# TopLevel.net
KiCad netlist of a schematic drawn in Altium Designer
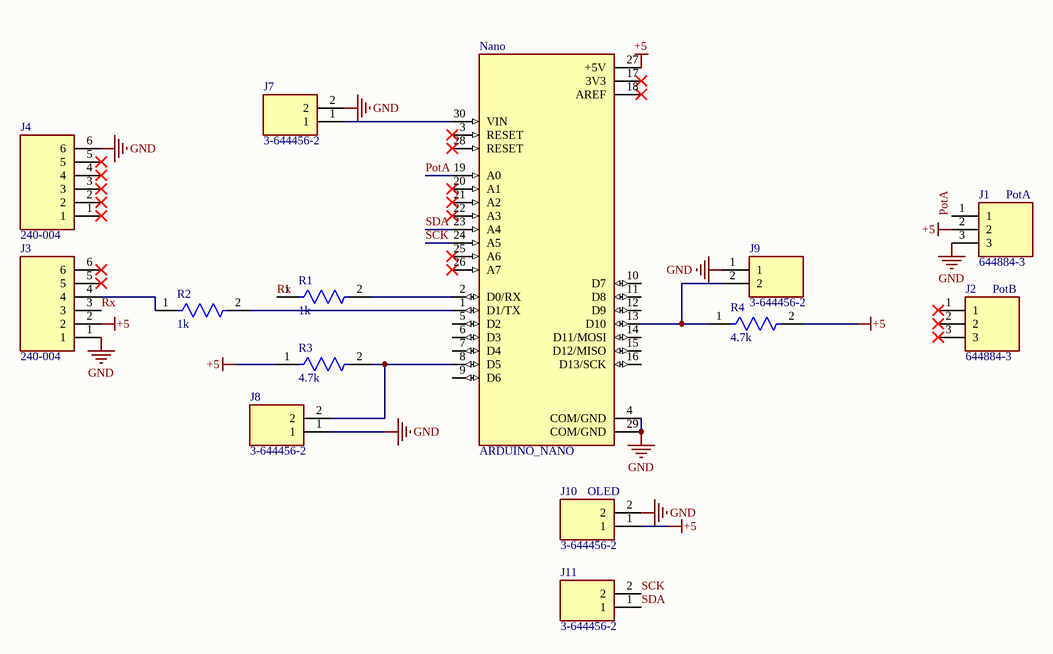
[diagram p0: TopLevel.SchDoc]

(export (version "E")
  (design (tool "Eeschema 10.0.6"))
  (components
    (comp (ref "J1")
      (value "644884-3")
      (footprint "TE_644884-3")
      (libsource (lib "Ryusei Kinosaki") (part "644884-3"))
    )
    (comp (ref "J2")
      (value "644884-3")
      (footprint "TE_644884-3")
      (libsource (lib "Ryusei Kinosaki") (part "644884-3"))
    )
    (comp (ref "J3")
      (value "240-004")
      (footprint "SamacSys:HDRV6W64P0X254_1X6_1524X254X909P")
      (description "Connector")
      (libsource (lib "*") (part "240-004"))
    )
    (comp (ref "J4")
      (value "240-004")
      (footprint "SamacSys:HDRV6W64P0X254_1X6_1524X254X909P")
      (description "Connector")
      (libsource (lib "*") (part "240-004"))
    )
    (comp (ref "J7")
      (value "3-644456-2")
      (footprint "TE_3-644456-2")
      (description "Connector Unshrouded Header HDR 2 Position 2.54mm Solder Straight Thru-Hole")
      (fields (field (name "MF") "TE Connectivity") (field (name "DIGI-KEY_PART_NUMBER") "A31112-ND"))
      (libsource (lib "Ryusei Kinosaki") (part "3-644456-2"))
    )
    (comp (ref "J8")
      (value "3-644456-2")
      (footprint "TE_3-644456-2")
      (description "Connector Unshrouded Header HDR 2 Position 2.54mm Solder Straight Thru-Hole")
      (fields (field (name "MF") "TE Connectivity") (field (name "DIGI-KEY_PART_NUMBER") "A31112-ND"))
      (libsource (lib "Ryusei Kinosaki") (part "3-644456-2"))
    )
    (comp (ref "J9")
      (value "3-644456-2")
      (footprint "TE_3-644456-2")
      (description "Connector Unshrouded Header HDR 2 Position 2.54mm Solder Straight Thru-Hole")
      (fields (field (name "MF") "TE Connectivity") (field (name "DIGI-KEY_PART_NUMBER") "A31112-ND"))
      (libsource (lib "") (part "3-644456-2_1"))
    )
    (comp (ref "J10")
      (value "3-644456-2")
      (footprint "TE_3-644456-2")
      (description "Connector Unshrouded Header HDR 2 Position 2.54mm Solder Straight Thru-Hole")
      (fields (field (name "MF") "TE Connectivity") (field (name "DIGI-KEY_PART_NUMBER") "A31112-ND"))
      (libsource (lib "Ryusei Kinosaki") (part "3-644456-2"))
    )
    (comp (ref "J11")
      (value "3-644456-2")
      (footprint "TE_3-644456-2")
      (description "Connector Unshrouded Header HDR 2 Position 2.54mm Solder Straight Thru-Hole")
      (fields (field (name "MF") "TE Connectivity") (field (name "DIGI-KEY_PART_NUMBER") "A31112-ND"))
      (libsource (lib "Ryusei Kinosaki") (part "3-644456-2"))
    )
    (comp (ref "Nano")
      (value "ARDUINO_NANO")
      (footprint "SHIELD_ARDUINO_NANO")
      (description "Small, complete, and breadboard-friendly board based on the ATmega328 (Arduino Nano 3.x)")
      (fields (field (name "MF") "Arduino") (field (name "MP") "Arduino Nano"))
      (libsource (lib "Ryusei Kinosaki") (part "ARDUINO_NANO"))
    )
    (comp (ref "R1")
      (value "MRS25000C1001FCT00")
      (footprint "FP-MRS25-MFG")
      (description "RES 1K OHM 0.6W 1% AXIAL")
      (fields (field (name "TOLERANCE") "1%") (field (name "RESISTANCE") "1k"))
      (libsource (lib "Altium Content Vault") (part "1029c3af85768c4190bb7ad29bc67b5"))
    )
    (comp (ref "R2")
      (value "MRS25000C1001FCT00")
      (footprint "FP-MRS25-MFG")
      (description "RES 1K OHM 0.6W 1% AXIAL")
      (fields (field (name "TOLERANCE") "1%") (field (name "RESISTANCE") "1k"))
      (libsource (lib "Altium Content Vault") (part "1029c3af85768c4190bb7ad29bc67b5"))
    )
    (comp (ref "R3")
      (value "MRS25000C1001FCT00")
      (footprint "FP-MRS25-MFG")
      (description "RES 1K OHM 0.6W 1% AXIAL")
      (fields (field (name "TOLERANCE") "1%") (field (name "RESISTANCE") "4.7k"))
      (libsource (lib "Altium Content Vault") (part "1029c3af85768c4190bb7ad29bc67b5"))
    )
    (comp (ref "R4")
      (value "MRS25000C1001FCT00")
      (footprint "FP-MRS25-MFG")
      (description "RES 1K OHM 0.6W 1% AXIAL")
      (fields (field (name "TOLERANCE") "1%") (field (name "RESISTANCE") "4.7k"))
      (libsource (lib "Altium Content Vault") (part "1029c3af85768c4190bb7ad29bc67b5"))
    )
  )
  (nets
    (net (code "1") (name "+5") (class "Default")
      (node (ref "J1") (pin "2") (pinfunction "2_2") (pintype "passive"))
      (node (ref "J10") (pin "1") (pinfunction "1_1") (pintype "passive"))
      (node (ref "J3") (pin "2") (pinfunction "2_2") (pintype "passive"))
      (node (ref "Nano") (pin "27") (pinfunction "+5V_27") (pintype "power_in"))
      (node (ref "R3") (pin "1") (pinfunction "1_1") (pintype "passive"))
      (node (ref "R4") (pin "2") (pinfunction "2_2") (pintype "passive"))
    )
    (net (code "2") (name "/PotA") (class "Default")
      (node (ref "J1") (pin "1") (pinfunction "1_1") (pintype "passive"))
      (node (ref "Nano") (pin "19") (pinfunction "A0_19") (pintype "input"))
    )
    (net (code "3") (name "/Rx") (class "Default")
      (node (ref "J3") (pin "3") (pinfunction "3_3") (pintype "passive"))
      (node (ref "R1") (pin "1") (pinfunction "1_1") (pintype "passive"))
    )
    (net (code "4") (name "/SCK") (class "Default")
      (node (ref "J11") (pin "2") (pinfunction "2_2") (pintype "passive"))
      (node (ref "Nano") (pin "24") (pinfunction "A5_24") (pintype "input"))
    )
    (net (code "5") (name "/SDA") (class "Default")
      (node (ref "J11") (pin "1") (pinfunction "1_1") (pintype "passive"))
      (node (ref "Nano") (pin "23") (pinfunction "A4_23") (pintype "input"))
    )
    (net (code "6") (name "GND") (class "Default")
      (node (ref "J1") (pin "3") (pinfunction "3_3") (pintype "passive"))
      (node (ref "J10") (pin "2") (pinfunction "2_2") (pintype "passive"))
      (node (ref "J3") (pin "1") (pinfunction "1_1") (pintype "passive"))
      (node (ref "J4") (pin "6") (pinfunction "6_6") (pintype "passive"))
      (node (ref "J7") (pin "2") (pinfunction "2_2") (pintype "passive"))
      (node (ref "J8") (pin "1") (pinfunction "1_1") (pintype "passive"))
      (node (ref "J9") (pin "1") (pinfunction "1_1") (pintype "passive"))
      (node (ref "Nano") (pin "29") (pinfunction "COM/GND_29") (pintype "power_in"))
      (node (ref "Nano") (pin "4") (pinfunction "COM/GND_4") (pintype "power_in"))
    )
    (net (code "7") (name "Net-(J3-Pad4)") (class "Default")
      (node (ref "J3") (pin "4") (pinfunction "4_4") (pintype "passive"))
      (node (ref "R2") (pin "1") (pinfunction "1_1") (pintype "passive"))
    )
    (net (code "8") (name "Net-(Nano-D0{slash}RX)") (class "Default")
      (node (ref "Nano") (pin "2") (pinfunction "D0/RX_2") (pintype "bidirectional"))
      (node (ref "R1") (pin "2") (pinfunction "2_2") (pintype "passive"))
    )
    (net (code "9") (name "Net-(Nano-D1{slash}TX)") (class "Default")
      (node (ref "Nano") (pin "1") (pinfunction "D1/TX_1") (pintype "bidirectional"))
      (node (ref "R2") (pin "2") (pinfunction "2_2") (pintype "passive"))
    )
    (net (code "10") (name "Net-(Nano-D5)") (class "Default")
      (node (ref "J8") (pin "2") (pinfunction "2_2") (pintype "passive"))
      (node (ref "Nano") (pin "8") (pinfunction "D5_8") (pintype "bidirectional"))
      (node (ref "R3") (pin "2") (pinfunction "2_2") (pintype "passive"))
    )
    (net (code "11") (name "Net-(Nano-D10)") (class "Default")
      (node (ref "J9") (pin "2") (pinfunction "2_2") (pintype "passive"))
      (node (ref "Nano") (pin "13") (pinfunction "D10_13") (pintype "bidirectional"))
      (node (ref "R4") (pin "1") (pinfunction "1_1") (pintype "passive"))
    )
    (net (code "12") (name "Net-(Nano-VIN)") (class "Default")
      (node (ref "J7") (pin "1") (pinfunction "1_1") (pintype "passive"))
      (node (ref "Nano") (pin "30") (pinfunction "VIN_30") (pintype "input"))
    )
    (net (code "13") (name "unconnected-(J2-Pad1)") (class "Default")
      (node (ref "J2") (pin "1") (pinfunction "1_1") (pintype "passive+no_connect"))
    )
    (net (code "14") (name "unconnected-(J2-Pad2)") (class "Default")
      (node (ref "J2") (pin "2") (pinfunction "2_2") (pintype "passive+no_connect"))
    )
    (net (code "15") (name "unconnected-(J2-Pad3)") (class "Default")
      (node (ref "J2") (pin "3") (pinfunction "3_3") (pintype "passive+no_connect"))
    )
    (net (code "16") (name "unconnected-(J3-Pad5)") (class "Default")
      (node (ref "J3") (pin "5") (pinfunction "5_5") (pintype "passive+no_connect"))
    )
    (net (code "17") (name "unconnected-(J3-Pad6)") (class "Default")
      (node (ref "J3") (pin "6") (pinfunction "6_6") (pintype "passive+no_connect"))
    )
    (net (code "18") (name "unconnected-(J4-Pad1)") (class "Default")
      (node (ref "J4") (pin "1") (pinfunction "1_1") (pintype "passive+no_connect"))
    )
    (net (code "19") (name "unconnected-(J4-Pad2)") (class "Default")
      (node (ref "J4") (pin "2") (pinfunction "2_2") (pintype "passive+no_connect"))
    )
    (net (code "20") (name "unconnected-(J4-Pad3)") (class "Default")
      (node (ref "J4") (pin "3") (pinfunction "3_3") (pintype "passive+no_connect"))
    )
    (net (code "21") (name "unconnected-(J4-Pad4)") (class "Default")
      (node (ref "J4") (pin "4") (pinfunction "4_4") (pintype "passive+no_connect"))
    )
    (net (code "22") (name "unconnected-(J4-Pad5)") (class "Default")
      (node (ref "J4") (pin "5") (pinfunction "5_5") (pintype "passive+no_connect"))
    )
    (net (code "23") (name "unconnected-(Nano-3V3-Pad17)") (class "Default")
      (node (ref "Nano") (pin "17") (pinfunction "3V3_17") (pintype "power_in+no_connect"))
    )
    (net (code "24") (name "unconnected-(Nano-A1-Pad20)") (class "Default")
      (node (ref "Nano") (pin "20") (pinfunction "A1_20") (pintype "input+no_connect"))
    )
    (net (code "25") (name "unconnected-(Nano-A2-Pad21)") (class "Default")
      (node (ref "Nano") (pin "21") (pinfunction "A2_21") (pintype "input+no_connect"))
    )
    (net (code "26") (name "unconnected-(Nano-A3-Pad22)") (class "Default")
      (node (ref "Nano") (pin "22") (pinfunction "A3_22") (pintype "input+no_connect"))
    )
    (net (code "27") (name "unconnected-(Nano-A6-Pad25)") (class "Default")
      (node (ref "Nano") (pin "25") (pinfunction "A6_25") (pintype "input+no_connect"))
    )
    (net (code "28") (name "unconnected-(Nano-A7-Pad26)") (class "Default")
      (node (ref "Nano") (pin "26") (pinfunction "A7_26") (pintype "input+no_connect"))
    )
    (net (code "29") (name "unconnected-(Nano-AREF-Pad18)") (class "Default")
      (node (ref "Nano") (pin "18") (pinfunction "AREF_18") (pintype "power_in+no_connect"))
    )
    (net (code "30") (name "unconnected-(Nano-D2-Pad5)") (class "Default")
      (node (ref "Nano") (pin "5") (pinfunction "D2_5") (pintype "bidirectional"))
    )
    (net (code "31") (name "unconnected-(Nano-D3-Pad6)") (class "Default")
      (node (ref "Nano") (pin "6") (pinfunction "D3_6") (pintype "bidirectional"))
    )
    (net (code "32") (name "unconnected-(Nano-D4-Pad7)") (class "Default")
      (node (ref "Nano") (pin "7") (pinfunction "D4_7") (pintype "bidirectional"))
    )
    (net (code "33") (name "unconnected-(Nano-D6-Pad9)") (class "Default")
      (node (ref "Nano") (pin "9") (pinfunction "D6_9") (pintype "bidirectional"))
    )
    (net (code "34") (name "unconnected-(Nano-D7-Pad10)") (class "Default")
      (node (ref "Nano") (pin "10") (pinfunction "D7_10") (pintype "bidirectional"))
    )
    (net (code "35") (name "unconnected-(Nano-D8-Pad11)") (class "Default")
      (node (ref "Nano") (pin "11") (pinfunction "D8_11") (pintype "bidirectional"))
    )
    (net (code "36") (name "unconnected-(Nano-D9-Pad12)") (class "Default")
      (node (ref "Nano") (pin "12") (pinfunction "D9_12") (pintype "bidirectional"))
    )
    (net (code "37") (name "unconnected-(Nano-D11{slash}MOSI-Pad14)") (class "Default")
      (node (ref "Nano") (pin "14") (pinfunction "D11/MOSI_14") (pintype "bidirectional"))
    )
    (net (code "38") (name "unconnected-(Nano-D12{slash}MISO-Pad15)") (class "Default")
      (node (ref "Nano") (pin "15") (pinfunction "D12/MISO_15") (pintype "bidirectional"))
    )
    (net (code "39") (name "unconnected-(Nano-D13{slash}SCK-Pad16)") (class "Default")
      (node (ref "Nano") (pin "16") (pinfunction "D13/SCK_16") (pintype "bidirectional"))
    )
    (net (code "40") (name "unconnected-(Nano-RESET-Pad3)") (class "Default")
      (node (ref "Nano") (pin "3") (pinfunction "RESET_3") (pintype "input+no_connect"))
    )
    (net (code "41") (name "unconnected-(Nano-RESET-Pad28)") (class "Default")
      (node (ref "Nano") (pin "28") (pinfunction "RESET_28") (pintype "input+no_connect"))
    )
  )
)
